# DM0249_Power.net
KiCad netlist of a schematic drawn in Altium Designer
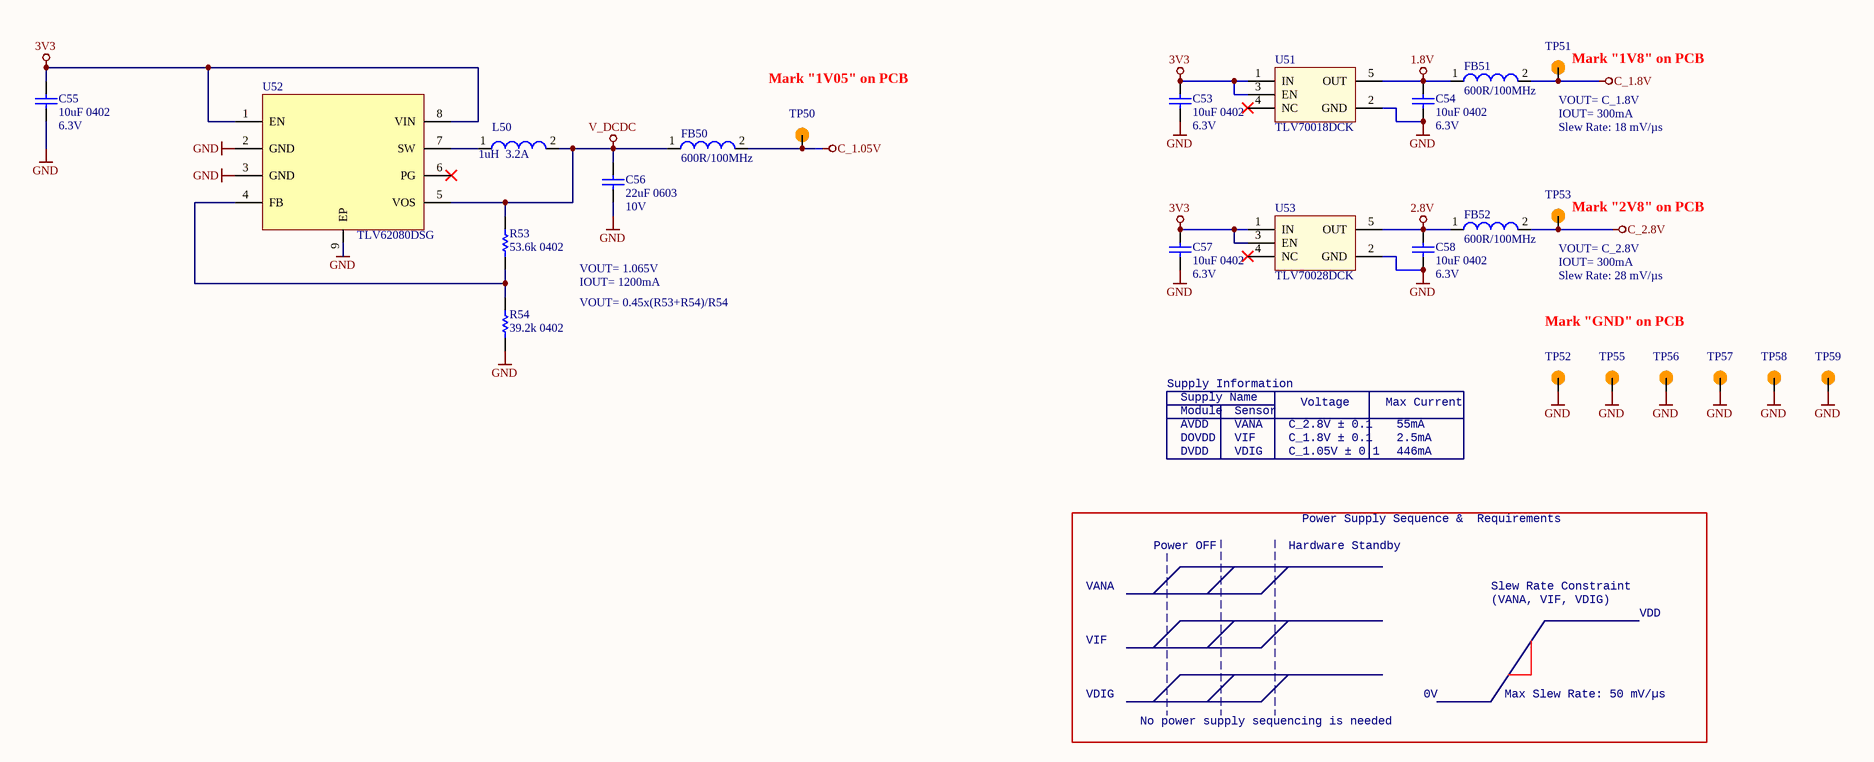
[diagram p0: DM0249_Power.SchDoc]

(export (version "E")
  (design (tool "Eeschema 10.0.6"))
  (components
    (comp (ref "C53")
      (value "10uF 0402")
      (footprint "CAP_Altium_Vault_Generic:CAPC0402(1005)70_N")
      (description "CAP CER 10UF 6.3V X5R 0402 20%")
      (fields (field (name "TOLERANCE") "20%") (field (name "VOLTAGE RATING") "6.3V"))
      (libsource (lib "LuxonisMaster") (part "GRM155R60J106ME15D"))
    )
    (comp (ref "C54")
      (value "10uF 0402")
      (footprint "CAP_Altium_Vault_Generic:CAPC0402(1005)70_N")
      (description "CAP CER 10UF 6.3V X5R 0402 20%")
      (fields (field (name "TOLERANCE") "20%") (field (name "VOLTAGE RATING") "6.3V"))
      (libsource (lib "LuxonisMaster") (part "GRM155R60J106ME15D"))
    )
    (comp (ref "C55")
      (value "10uF 0402")
      (footprint "CAP_Altium_Vault_Generic:CAPC0402(1005)70_N")
      (description "CAP CER 10UF 6.3V X5R 0402 20%")
      (fields (field (name "TOLERANCE") "20%") (field (name "VOLTAGE RATING") "6.3V"))
      (libsource (lib "LuxonisMaster") (part "GRM155R60J106ME15D"))
    )
    (comp (ref "C56")
      (value "22uF 0603")
      (footprint "CAP_Altium_Vault_Generic:CAPC0603(1608)100_N")
      (description "CAP CER 22UF 10V X5R 0603 20%")
      (fields (field (name "TOLERANCE") "20%") (field (name "VOLTAGE RATING") "10V"))
      (libsource (lib "LuxonisMaster") (part "GRM188R61A226ME15D"))
    )
    (comp (ref "C57")
      (value "10uF 0402")
      (footprint "CAP_Altium_Vault_Generic:CAPC0402(1005)70_N")
      (description "CAP CER 10UF 6.3V X5R 0402 20%")
      (fields (field (name "TOLERANCE") "20%") (field (name "VOLTAGE RATING") "6.3V"))
      (libsource (lib "LuxonisMaster") (part "GRM155R60J106ME15D"))
    )
    (comp (ref "C58")
      (value "10uF 0402")
      (footprint "CAP_Altium_Vault_Generic:CAPC0402(1005)70_N")
      (description "CAP CER 10UF 6.3V X5R 0402 20%")
      (fields (field (name "TOLERANCE") "20%") (field (name "VOLTAGE RATING") "6.3V"))
      (libsource (lib "LuxonisMaster") (part "GRM155R60J106ME15D"))
    )
    (comp (ref "FB50")
      (value "600R/100MHz")
      (footprint "LuxonisMaster:2508056017Y2")
      (description "FERRITE BEAD, 0.1OHM, 2A, 0805, 600R/100MHz")
      (fields (field (name "TOLERANCE") "25%"))
      (libsource (lib "LuxonisMaster") (part "2508056017Y2"))
    )
    (comp (ref "FB51")
      (value "600R/100MHz")
      (footprint "LuxonisMaster:2508056017Y2")
      (description "FERRITE BEAD, 0.1OHM, 2A, 0805, 600R/100MHz")
      (fields (field (name "TOLERANCE") "25%"))
      (libsource (lib "LuxonisMaster") (part "2508056017Y2"))
    )
    (comp (ref "FB52")
      (value "600R/100MHz")
      (footprint "LuxonisMaster:2508056017Y2")
      (description "FERRITE BEAD, 0.1OHM, 2A, 0805, 600R/100MHz")
      (fields (field (name "TOLERANCE") "25%"))
      (libsource (lib "LuxonisMaster") (part "2508056017Y2"))
    )
    (comp (ref "L50")
      (value "1uH, 3.2A, 20%")
      (footprint "LuxonisMaster:DFE252012P-1R0M=P2")
      (description "FIXED IND 1UH 3.2A 42 MOHM SMD")
      (fields
        (field (name "MANUFACTURER") "Murata")
        (field (name "MANUFACTURER PART NUMBER") "DFE252012P-1R0M=P2")
        (field (name "MAX DC CURRENT") "3.2A")
        (field (name "INDUCTANCE") "1uH")
      )
      (libsource (lib "LuxonisMaster") (part "DFE252012P-1R0M=P2"))
    )
    (comp (ref "R53")
      (value "53.6k 0402")
      (footprint "RES_Altium_Vault_Generic:RESC0402(1005)_N")
      (description "RES SMD 53.6K OHM 1% 1/16W 0402")
      (fields (field (name "TOLERANCE") "1%"))
      (libsource (lib "LuxonisMaster") (part "CRCW040253K6FKED"))
    )
    (comp (ref "R54")
      (value "39.2k 0402")
      (footprint "RES_Altium_Vault_Generic:RESC0402(1005)_N")
      (description "RES SMD 39.2K OHM 1% 1/16W 0402")
      (fields (field (name "TOLERANCE") "1%"))
      (libsource (lib "LuxonisMaster") (part "CRCW040239K2FKED"))
    )
    (comp (ref "TP50")
      (value "TP100_150_NS")
      (footprint "LuxonisMaster:TP100_150_NS")
      (libsource (lib "LuxonisMaster") (part "TEST_POINT"))
    )
    (comp (ref "TP51")
      (value "TP100_150_NS")
      (footprint "LuxonisMaster:TP100_150_NS")
      (libsource (lib "LuxonisMaster") (part "TEST_POINT"))
    )
    (comp (ref "TP52")
      (value "TP100_150_NS")
      (footprint "LuxonisMaster:TP100_150_NS")
      (libsource (lib "LuxonisMaster") (part "TEST_POINT"))
    )
    (comp (ref "TP53")
      (value "TP100_150_NS")
      (footprint "LuxonisMaster:TP100_150_NS")
      (libsource (lib "LuxonisMaster") (part "TEST_POINT"))
    )
    (comp (ref "TP55")
      (value "TP100_150_NS")
      (footprint "LuxonisMaster:TP100_150_NS")
      (libsource (lib "LuxonisMaster") (part "TEST_POINT"))
    )
    (comp (ref "TP56")
      (value "TP100_150_NS")
      (footprint "LuxonisMaster:TP100_150_NS")
      (libsource (lib "LuxonisMaster") (part "TEST_POINT"))
    )
    (comp (ref "TP57")
      (value "TP100_150_NS")
      (footprint "LuxonisMaster:TP100_150_NS")
      (libsource (lib "LuxonisMaster") (part "TEST_POINT"))
    )
    (comp (ref "TP58")
      (value "TP100_150_NS")
      (footprint "LuxonisMaster:TP100_150_NS")
      (libsource (lib "LuxonisMaster") (part "TEST_POINT"))
    )
    (comp (ref "TP59")
      (value "TP100_150_NS")
      (footprint "LuxonisMaster:TP100_150_NS")
      (libsource (lib "LuxonisMaster") (part "TEST_POINT"))
    )
    (comp (ref "U51")
      (value "TLV70018DCK")
      (footprint "LuxonisMaster:TLV70018DCK")
      (description "IC REG LINEAR 1.8V 200MA SC70-5 Linear Voltage Regulator IC  1 Output  200mA SC-70-5")
      (libsource (lib "LuxonisMaster") (part "TLV70018DCK"))
    )
    (comp (ref "U52")
      (value "TLV62080DSG")
      (footprint "LuxonisMaster:TLV62080DSG")
      (description "IC REG BUCK ADJ 1.2A SYNC 8WSON")
      (libsource (lib "LuxonisMaster") (part "TLV62080DSG"))
    )
    (comp (ref "U53")
      (value "TLV70028DCK")
      (footprint "LuxonisMaster:TLV70028DCK")
      (description "IC REG LINEAR 2.8V 200MA SC70-5 Linear Voltage Regulator IC  1 Output  200mA SC-70-5")
      (libsource (lib "LuxonisMaster") (part "TLV70028DCK"))
    )
  )
  (nets
    (net (code "1") (name "1.8V") (class "Default")
      (node (ref "C54") (pin "2") (pinfunction "2_2") (pintype "passive"))
      (node (ref "FB51") (pin "1") (pinfunction "1_1") (pintype "passive"))
      (node (ref "U51") (pin "5") (pinfunction "OUT_5") (pintype "passive"))
    )
    (net (code "2") (name "2.8V") (class "Default")
      (node (ref "C58") (pin "2") (pinfunction "2_2") (pintype "passive"))
      (node (ref "FB52") (pin "1") (pinfunction "1_1") (pintype "passive"))
      (node (ref "U53") (pin "5") (pinfunction "OUT_5") (pintype "passive"))
    )
    (net (code "3") (name "3V3") (class "Default")
      (node (ref "C53") (pin "2") (pinfunction "2_2") (pintype "passive"))
      (node (ref "C55") (pin "2") (pinfunction "2_2") (pintype "passive"))
      (node (ref "C57") (pin "2") (pinfunction "2_2") (pintype "passive"))
      (node (ref "U51") (pin "1") (pinfunction "IN_1") (pintype "passive"))
      (node (ref "U51") (pin "3") (pinfunction "EN_3") (pintype "passive"))
      (node (ref "U52") (pin "1") (pinfunction "EN_1") (pintype "passive"))
      (node (ref "U52") (pin "8") (pinfunction "VIN_8") (pintype "passive"))
      (node (ref "U53") (pin "1") (pinfunction "IN_1") (pintype "passive"))
      (node (ref "U53") (pin "3") (pinfunction "EN_3") (pintype "passive"))
    )
    (net (code "4") (name "C_1.05V") (class "Default")
      (node (ref "FB50") (pin "2") (pinfunction "2_2") (pintype "passive"))
      (node (ref "TP50") (pin "1") (pintype "passive"))
    )
    (net (code "5") (name "C_1.8V") (class "Default")
      (node (ref "FB51") (pin "2") (pinfunction "2_2") (pintype "passive"))
      (node (ref "TP51") (pin "1") (pintype "passive"))
    )
    (net (code "6") (name "C_2.8V") (class "Default")
      (node (ref "FB52") (pin "2") (pinfunction "2_2") (pintype "passive"))
      (node (ref "TP53") (pin "1") (pintype "passive"))
    )
    (net (code "7") (name "GND") (class "Default")
      (node (ref "C53") (pin "1") (pinfunction "1_1") (pintype "passive"))
      (node (ref "C54") (pin "1") (pinfunction "1_1") (pintype "passive"))
      (node (ref "C55") (pin "1") (pinfunction "1_1") (pintype "passive"))
      (node (ref "C56") (pin "1") (pinfunction "1_1") (pintype "passive"))
      (node (ref "C57") (pin "1") (pinfunction "1_1") (pintype "passive"))
      (node (ref "C58") (pin "1") (pinfunction "1_1") (pintype "passive"))
      (node (ref "R54") (pin "1") (pinfunction "1_1") (pintype "passive"))
      (node (ref "TP52") (pin "1") (pintype "passive"))
      (node (ref "TP55") (pin "1") (pintype "passive"))
      (node (ref "TP56") (pin "1") (pintype "passive"))
      (node (ref "TP57") (pin "1") (pintype "passive"))
      (node (ref "TP58") (pin "1") (pintype "passive"))
      (node (ref "TP59") (pin "1") (pintype "passive"))
      (node (ref "U51") (pin "2") (pinfunction "GND_2") (pintype "passive"))
      (node (ref "U52") (pin "2") (pinfunction "GND_2") (pintype "passive"))
      (node (ref "U52") (pin "3") (pinfunction "GND_3") (pintype "passive"))
      (node (ref "U52") (pin "9") (pinfunction "EP_9") (pintype "passive"))
      (node (ref "U53") (pin "2") (pinfunction "GND_2") (pintype "passive"))
    )
    (net (code "8") (name "Net-(U52-FB)") (class "Default")
      (node (ref "R53") (pin "1") (pinfunction "1_1") (pintype "passive"))
      (node (ref "R54") (pin "2") (pinfunction "2_2") (pintype "passive"))
      (node (ref "U52") (pin "4") (pinfunction "FB_4") (pintype "passive"))
    )
    (net (code "9") (name "Net-(U52-SW)") (class "Default")
      (node (ref "L50") (pin "1") (pinfunction "1_1") (pintype "passive"))
      (node (ref "U52") (pin "7") (pinfunction "SW_7") (pintype "passive"))
    )
    (net (code "10") (name "V_DCDC") (class "Default")
      (node (ref "C56") (pin "2") (pinfunction "2_2") (pintype "passive"))
      (node (ref "FB50") (pin "1") (pinfunction "1_1") (pintype "passive"))
      (node (ref "L50") (pin "2") (pinfunction "2_2") (pintype "passive"))
      (node (ref "R53") (pin "2") (pinfunction "2_2") (pintype "passive"))
      (node (ref "U52") (pin "5") (pinfunction "VOS_5") (pintype "passive"))
    )
    (net (code "11") (name "unconnected-(U51-NC-Pad4)") (class "Default")
      (node (ref "U51") (pin "4") (pinfunction "NC_4") (pintype "passive+no_connect"))
    )
    (net (code "12") (name "unconnected-(U52-PG-Pad6)") (class "Default")
      (node (ref "U52") (pin "6") (pinfunction "PG_6") (pintype "passive+no_connect"))
    )
    (net (code "13") (name "unconnected-(U53-NC-Pad4)") (class "Default")
      (node (ref "U53") (pin "4") (pinfunction "NC_4") (pintype "passive+no_connect"))
    )
  )
)
